# PWR_TLV62084.net
KiCad netlist of a schematic drawn in Altium Designer
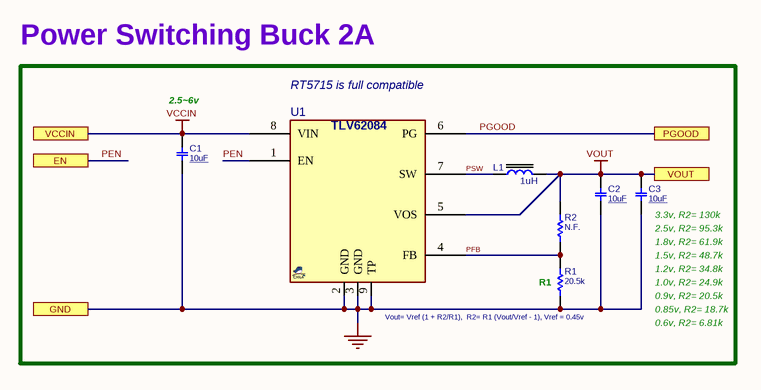
[diagram p0: PWR_TLV62084.SchDoc]

(export (version "E")
  (design (tool "Eeschema 10.0.6"))
  (components
    (comp (ref "C1")
      (value "10uF")
      (footprint "C0402")
      (description "CAP, MLCC")
      (libsource (lib "passive_smd") (part "CAP_SMD_MLCC"))
    )
    (comp (ref "C2")
      (value "10uF")
      (footprint "C0402")
      (description "CAP, MLCC")
      (libsource (lib "passive_smd") (part "CAP_SMD_MLCC"))
    )
    (comp (ref "C3")
      (value "10uF")
      (footprint "C0402")
      (description "CAP, MLCC")
      (libsource (lib "passive_smd") (part "CAP_SMD_MLCC"))
    )
    (comp (ref "L1")
      (value "1uH")
      (footprint "L0806")
      (description "INDUCTOR, POWER, SMD")
      (fields (field (name "MANF") "Murata") (field (name "MANF_P#") "DFE201610E-1R0M"))
      (libsource (lib "passive_smd") (part "INDPWR_SMD"))
    )
    (comp (ref "R1")
      (value "20.5k")
      (footprint "R0402")
      (description "RESISTOR, SMD")
      (libsource (lib "passive_smd") (part "RES_SMD"))
    )
    (comp (ref "R2")
      (value "N.F.")
      (footprint "R0402")
      (description "RESISTOR, SMD")
      (libsource (lib "passive_smd") (part "RES_SMD"))
    )
    (comp (ref "U1")
      (value "TLV62084")
      (footprint "SON50_8T_2020")
      (description "REG, Switching, Buck, 2A, ADJ, 2MHz, 2.5~6VIN, SON-8")
      (fields (field (name "MANF_P#") "TLV62084DSG") (field (name "MANF") "Texas Instruments"))
      (libsource (lib "pwr_switching_buck") (part "VREG_TLV62084_SON8"))
    )
  )
  (nets
    (net (code "1") (name "/PEN") (class "Default")
      (node (ref "U1") (pin "1") (pinfunction "EN_1") (pintype "passive"))
    )
    (net (code "2") (name "/PFB") (class "Default")
      (node (ref "R1") (pin "2") (pinfunction "2_2") (pintype "passive"))
      (node (ref "R2") (pin "1") (pinfunction "1_1") (pintype "passive"))
      (node (ref "U1") (pin "4") (pinfunction "FB_4") (pintype "passive"))
    )
    (net (code "3") (name "/PGOOD") (class "Default")
      (node (ref "U1") (pin "6") (pinfunction "PG_6") (pintype "passive"))
    )
    (net (code "4") (name "/PSW") (class "Default")
      (node (ref "L1") (pin "1") (pinfunction "1_1") (pintype "passive"))
      (node (ref "U1") (pin "7") (pinfunction "SW_7") (pintype "passive"))
    )
    (net (code "5") (name "GND") (class "Default")
      (node (ref "C1") (pin "2") (pinfunction "2_2") (pintype "passive"))
      (node (ref "C2") (pin "2") (pinfunction "2_2") (pintype "passive"))
      (node (ref "C3") (pin "2") (pinfunction "2_2") (pintype "passive"))
      (node (ref "R1") (pin "1") (pinfunction "1_1") (pintype "passive"))
      (node (ref "U1") (pin "2") (pinfunction "GND_2") (pintype "passive"))
      (node (ref "U1") (pin "3") (pinfunction "GND_3") (pintype "passive"))
      (node (ref "U1") (pin "9") (pinfunction "TP_9") (pintype "passive"))
    )
    (net (code "6") (name "VCCIN") (class "Default")
      (node (ref "C1") (pin "1") (pinfunction "1_1") (pintype "passive"))
      (node (ref "U1") (pin "8") (pinfunction "VIN_8") (pintype "passive"))
    )
    (net (code "7") (name "VOUT") (class "Default")
      (node (ref "C2") (pin "1") (pinfunction "1_1") (pintype "passive"))
      (node (ref "C3") (pin "1") (pinfunction "1_1") (pintype "passive"))
      (node (ref "L1") (pin "2") (pinfunction "2_2") (pintype "passive"))
      (node (ref "R2") (pin "2") (pinfunction "2_2") (pintype "passive"))
      (node (ref "U1") (pin "5") (pinfunction "VOS_5") (pintype "passive"))
    )
  )
)
